# Bridge_DS2482.net
KiCad netlist of a schematic drawn in EAGLE
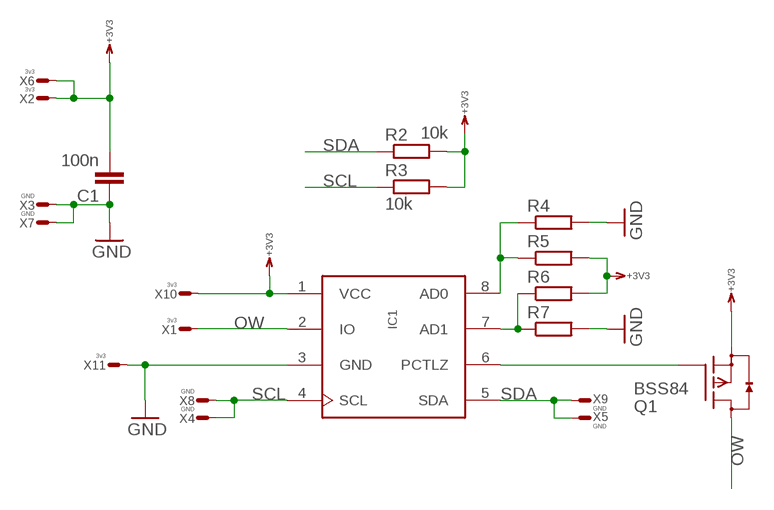
[diagram p0: schematic, sheet 1]

(export (version "E")
  (design (tool "Eeschema 10.0.6"))
  (components
    (comp (ref "C1")
      (value "100n")
      (footprint "eagle-import:0603")
      (libsource (lib "eagle-import") (part "C0603"))
    )
    (comp (ref "IC1")
      (value "DS2482S")
      (footprint "eagle-import:SO8")
      (libsource (lib "eagle-import") (part "DS2482S"))
    )
    (comp (ref "Q1")
      (value "BSS84")
      (footprint "eagle-import:SOT23")
      (libsource (lib "eagle-import") (part "FET-PDSOT23"))
    )
    (comp (ref "R2")
      (value "10k")
      (footprint "eagle-import:0603")
      (libsource (lib "eagle-import") (part "R0603"))
    )
    (comp (ref "R3")
      (value "10k")
      (footprint "eagle-import:0603")
      (libsource (lib "eagle-import") (part "R0603"))
    )
    (comp (ref "R4")
      (value "R0603")
      (footprint "eagle-import:0603")
      (libsource (lib "eagle-import") (part "R0603"))
    )
    (comp (ref "R5")
      (value "R0603")
      (footprint "eagle-import:0603")
      (libsource (lib "eagle-import") (part "R0603"))
    )
    (comp (ref "R6")
      (value "R0603")
      (footprint "eagle-import:0603")
      (libsource (lib "eagle-import") (part "R0603"))
    )
    (comp (ref "R7")
      (value "R0603")
      (footprint "eagle-import:0603")
      (libsource (lib "eagle-import") (part "R0603"))
    )
    (comp (ref "X1")
      (value "3v3")
      (footprint "eagle-import:T1.6_0.9")
      (libsource (lib "eagle-import") (part "WIREPADT1.6/0.9"))
    )
    (comp (ref "X2")
      (value "3v3")
      (footprint "eagle-import:T1.6_0.9")
      (libsource (lib "eagle-import") (part "WIREPADT1.6/0.9"))
    )
    (comp (ref "X3")
      (value "GND")
      (footprint "eagle-import:T1.6_0.9")
      (libsource (lib "eagle-import") (part "WIREPADT1.6/0.9"))
    )
    (comp (ref "X4")
      (value "GND")
      (footprint "eagle-import:T1.6_0.9")
      (libsource (lib "eagle-import") (part "WIREPADT1.6/0.9"))
    )
    (comp (ref "X5")
      (value "GND")
      (footprint "eagle-import:T1.6_0.9")
      (libsource (lib "eagle-import") (part "WIREPADT1.6/0.9"))
    )
    (comp (ref "X6")
      (value "3v3")
      (footprint "eagle-import:T1.6_0.9")
      (libsource (lib "eagle-import") (part "WIREPADT1.6/0.9"))
    )
    (comp (ref "X7")
      (value "GND")
      (footprint "eagle-import:T1.6_0.9")
      (libsource (lib "eagle-import") (part "WIREPADT1.6/0.9"))
    )
    (comp (ref "X8")
      (value "GND")
      (footprint "eagle-import:T1.6_0.9")
      (libsource (lib "eagle-import") (part "WIREPADT1.6/0.9"))
    )
    (comp (ref "X9")
      (value "GND")
      (footprint "eagle-import:T1.6_0.9")
      (libsource (lib "eagle-import") (part "WIREPADT1.6/0.9"))
    )
    (comp (ref "X10")
      (value "3v3")
      (footprint "eagle-import:T1.6_0.9")
      (libsource (lib "eagle-import") (part "WIREPADT1.6/0.9"))
    )
    (comp (ref "X11")
      (value "3v3")
      (footprint "eagle-import:T1.6_0.9")
      (libsource (lib "eagle-import") (part "WIREPADT1.6/0.9"))
    )
  )
  (nets
    (net (code "1") (name "+3V3") (class "Default")
      (node (ref "C1") (pin "2") (pinfunction "2_2") (pintype "passive"))
      (node (ref "IC1") (pin "1") (pinfunction "VCC_1") (pintype "bidirectional"))
      (node (ref "Q1") (pin "2") (pinfunction "S_2") (pintype "passive"))
      (node (ref "R2") (pin "2") (pinfunction "2_2") (pintype "passive"))
      (node (ref "R3") (pin "2") (pinfunction "2_2") (pintype "passive"))
      (node (ref "R5") (pin "2") (pinfunction "2_2") (pintype "passive"))
      (node (ref "R6") (pin "2") (pinfunction "2_2") (pintype "passive"))
      (node (ref "X10") (pin "1") (pinfunction "S_1") (pintype "passive"))
      (node (ref "X2") (pin "1") (pinfunction "S_1") (pintype "passive"))
      (node (ref "X6") (pin "1") (pinfunction "S_1") (pintype "passive"))
    )
    (net (code "2") (name "/OW") (class "Default")
      (node (ref "IC1") (pin "2") (pinfunction "IO_2") (pintype "bidirectional"))
      (node (ref "Q1") (pin "3") (pinfunction "D_3") (pintype "passive"))
      (node (ref "X1") (pin "1") (pinfunction "S_1") (pintype "passive"))
    )
    (net (code "3") (name "/SCL") (class "Default")
      (node (ref "IC1") (pin "4") (pinfunction "SCL_4") (pintype "bidirectional"))
      (node (ref "R3") (pin "1") (pinfunction "1_1") (pintype "passive"))
      (node (ref "X4") (pin "1") (pinfunction "S_1") (pintype "passive"))
      (node (ref "X8") (pin "1") (pinfunction "S_1") (pintype "passive"))
    )
    (net (code "4") (name "/SDA") (class "Default")
      (node (ref "IC1") (pin "5") (pinfunction "SDA_5") (pintype "bidirectional"))
      (node (ref "R2") (pin "1") (pinfunction "1_1") (pintype "passive"))
      (node (ref "X5") (pin "1") (pinfunction "S_1") (pintype "passive"))
      (node (ref "X9") (pin "1") (pinfunction "S_1") (pintype "passive"))
    )
    (net (code "5") (name "GND") (class "Default")
      (node (ref "C1") (pin "1") (pinfunction "1_1") (pintype "passive"))
      (node (ref "IC1") (pin "3") (pinfunction "GND_3") (pintype "bidirectional"))
      (node (ref "R4") (pin "2") (pinfunction "2_2") (pintype "passive"))
      (node (ref "R7") (pin "2") (pinfunction "2_2") (pintype "passive"))
      (node (ref "X11") (pin "1") (pinfunction "S_1") (pintype "passive"))
      (node (ref "X3") (pin "1") (pinfunction "S_1") (pintype "passive"))
      (node (ref "X7") (pin "1") (pinfunction "S_1") (pintype "passive"))
    )
    (net (code "6") (name "Net-(IC1-AD0)") (class "Default")
      (node (ref "IC1") (pin "8") (pinfunction "AD0_8") (pintype "input"))
      (node (ref "R4") (pin "1") (pinfunction "1_1") (pintype "passive"))
      (node (ref "R5") (pin "1") (pinfunction "1_1") (pintype "passive"))
    )
    (net (code "7") (name "Net-(IC1-AD1)") (class "Default")
      (node (ref "IC1") (pin "7") (pinfunction "AD1_7") (pintype "input"))
      (node (ref "R6") (pin "1") (pinfunction "1_1") (pintype "passive"))
      (node (ref "R7") (pin "1") (pinfunction "1_1") (pintype "passive"))
    )
    (net (code "8") (name "Net-(IC1-PCTLZ)") (class "Default")
      (node (ref "IC1") (pin "6") (pinfunction "PCTLZ_6") (pintype "output"))
      (node (ref "Q1") (pin "1") (pinfunction "G_1") (pintype "passive"))
    )
  )
)
